# Schematic_v1.net
KiCad netlist of a schematic drawn in Altium Designer
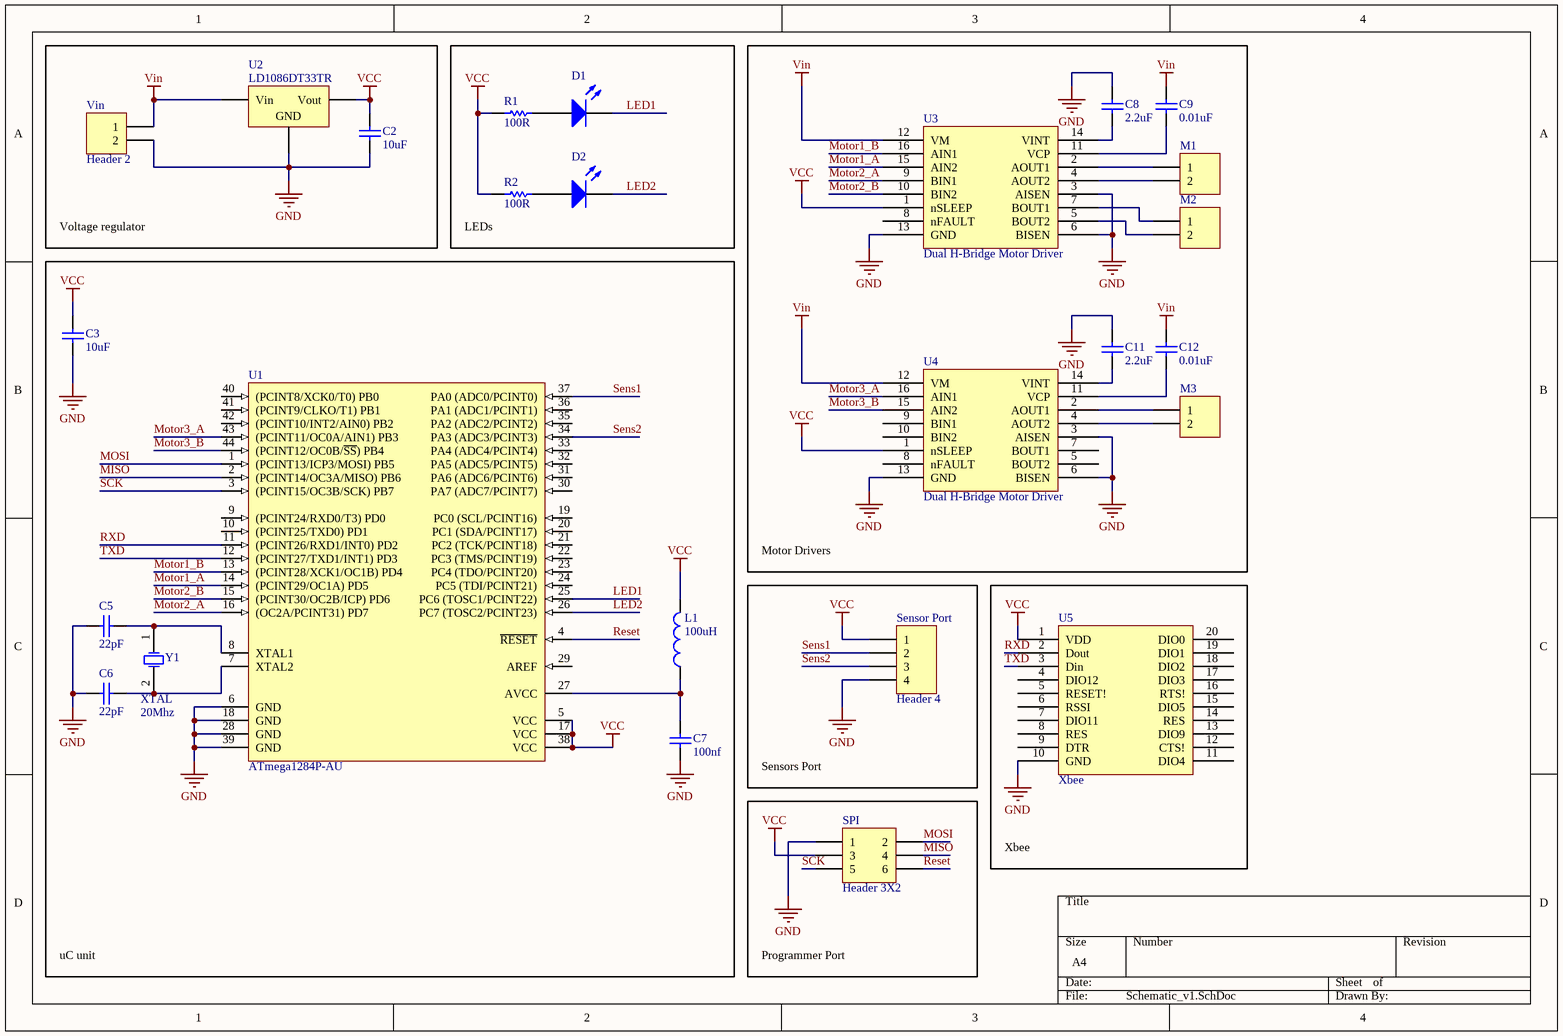
[diagram p0: Schematic_v1.SchDoc]

(export (version "E")
  (design (tool "Eeschema 10.0.6"))
  (components
    (comp (ref "C2")
      (value "10uF")
      (footprint "C1206")
      (description "Capacitor")
      (fields (field (name "Comment") "Cap") (field (name "PUBLISHER") "Altium Limited"))
      (libsource (lib "Miscellaneous Devices") (part "Cap"))
    )
    (comp (ref "C3")
      (value "10uF")
      (footprint "C1206")
      (description "Capacitor")
      (fields (field (name "Comment") "Cap") (field (name "PUBLISHER") "Altium Limited"))
      (libsource (lib "Miscellaneous Devices") (part "Cap"))
    )
    (comp (ref "C5")
      (value "22pF")
      (footprint "C1206")
      (description "Capacitor")
      (fields (field (name "Comment") "Cap") (field (name "PUBLISHER") "Altium Limited"))
      (libsource (lib "Miscellaneous Devices") (part "Cap"))
    )
    (comp (ref "C6")
      (value "22pF")
      (footprint "C1206")
      (description "Capacitor")
      (fields (field (name "Comment") "Cap") (field (name "PUBLISHER") "Altium Limited"))
      (libsource (lib "Miscellaneous Devices") (part "Cap"))
    )
    (comp (ref "C7")
      (value "100nf")
      (footprint "C1206")
      (description "Capacitor")
      (fields (field (name "Comment") "Cap") (field (name "PUBLISHER") "Altium Limited"))
      (libsource (lib "Miscellaneous Devices") (part "Cap"))
    )
    (comp (ref "C8")
      (value "2.2uF")
      (footprint "C1206")
      (description "Capacitor")
      (fields (field (name "Comment") "Cap") (field (name "PUBLISHER") "Altium Limited"))
      (libsource (lib "Miscellaneous Devices") (part "Cap"))
    )
    (comp (ref "C9")
      (value "0.01uF")
      (footprint "C1206")
      (description "Capacitor")
      (fields (field (name "Comment") "Cap") (field (name "PUBLISHER") "Altium Limited"))
      (libsource (lib "Miscellaneous Devices") (part "Cap"))
    )
    (comp (ref "C11")
      (value "2.2uF")
      (footprint "C1206")
      (description "Capacitor")
      (fields (field (name "Comment") "Cap") (field (name "PUBLISHER") "Altium Limited"))
      (libsource (lib "Miscellaneous Devices") (part "Cap"))
    )
    (comp (ref "C12")
      (value "0.01uF")
      (footprint "C1206")
      (description "Capacitor")
      (fields (field (name "Comment") "Cap") (field (name "PUBLISHER") "Altium Limited"))
      (libsource (lib "Miscellaneous Devices") (part "Cap"))
    )
    (comp (ref "D1")
      (value "LED0")
      (footprint "1206")
      (description "Typical INFRARED GaAs LED")
      (fields (field (name "PUBLISHER") "Altium Limited"))
      (libsource (lib "Miscellaneous Devices") (part "LED0"))
    )
    (comp (ref "D2")
      (value "LED0")
      (footprint "1206")
      (description "Typical INFRARED GaAs LED")
      (fields (field (name "PUBLISHER") "Altium Limited"))
      (libsource (lib "Miscellaneous Devices") (part "LED0"))
    )
    (comp (ref "L1")
      (value "100uH")
      (footprint "C0805")
      (description "Inductor")
      (fields (field (name "PUBLISHER") "Altium Limited"))
      (libsource (lib "Miscellaneous Devices") (part "Inductor"))
    )
    (comp (ref "M1")
      (value "Header 2")
      (footprint "SMD Header 2")
      (description "Header, 2-Pin")
      (fields (field (name "PUBLISHER") "Altium Limited"))
      (libsource (lib "Miscellaneous Connectors") (part "Header 2"))
    )
    (comp (ref "M2")
      (value "Header 2")
      (footprint "SMD Header 2")
      (description "Header, 2-Pin")
      (fields (field (name "PUBLISHER") "Altium Limited"))
      (libsource (lib "Miscellaneous Connectors") (part "Header 2"))
    )
    (comp (ref "M3")
      (value "Header 2")
      (footprint "SMD Header 2")
      (description "Header, 2-Pin")
      (fields (field (name "PUBLISHER") "Altium Limited"))
      (libsource (lib "Miscellaneous Connectors") (part "Header 2"))
    )
    (comp (ref "R1")
      (value "100R")
      (footprint "8-1206")
      (description "Resistor")
      (fields (field (name "Comment") "Res1") (field (name "PUBLISHER") "Altium Limited"))
      (libsource (lib "Miscellaneous Devices") (part "Res1"))
    )
    (comp (ref "R2")
      (value "100R")
      (footprint "8-1206")
      (description "Resistor")
      (fields (field (name "Comment") "Res1") (field (name "PUBLISHER") "Altium Limited"))
      (libsource (lib "Miscellaneous Devices") (part "Res1"))
    )
    (comp (ref "Sensor Port")
      (value "Header 4")
      (footprint "SMD HEADER 4")
      (description "Header, 4-Pin")
      (fields (field (name "PUBLISHER") "Altium Limited"))
      (libsource (lib "Miscellaneous Connectors") (part "Header 4"))
    )
    (comp (ref "SPI")
      (value "Header 3X2")
      (footprint "SMD MALE HEADER 3x2")
      (description "Header, 3-Pin, Dual row")
      (fields (field (name "PUBLISHER") "Altium Limited"))
      (libsource (lib "Miscellaneous Connectors") (part "Header 3X2"))
    )
    (comp (ref "U1")
      (value "ATmega1284P-AU")
      (footprint "44A_N")
      (description "20 MHz 8-bit AVR Microcontroller with 128KB Flash, 44-Pin TQFP Pkg, Industrial Temp")
      (fields (field (name "PUBLISHER") "Altium Limited"))
      (libsource (lib "Atmel Communication ICs") (part "ATmega1284P-AU"))
    )
    (comp (ref "U2")
      (value "LD1086DT33TR")
      (footprint "TO-252AA_M")
      (description "Voltage Regulator")
      (fields (field (name "PUBLISHER") "Altium Limited"))
      (libsource (lib "Miscellaneous Devices") (part "Volt Reg"))
    )
    (comp (ref "U3")
      (value "Dual H-Bridge Motor Driver")
      (footprint "TSSOP16_M")
      (libsource (lib "MySchLib") (part "DRV8833"))
    )
    (comp (ref "U4")
      (value "Dual H-Bridge Motor Driver")
      (footprint "TSSOP16_M")
      (libsource (lib "MySchLib") (part "DRV8833"))
    )
    (comp (ref "U5") (value "Xbee") (footprint "Xbee") (libsource (lib "MySchLib") (part "Xbee")))
    (comp (ref "Vin")
      (value "Header 2")
      (footprint "SMD Header 2")
      (description "Header, 2-Pin")
      (fields (field (name "PUBLISHER") "Altium Limited"))
      (libsource (lib "") (part "Header 2_1"))
    )
    (comp (ref "Y1")
      (value "XTAL")
      (footprint "ECX-64A")
      (description "Crystal")
      (fields (field (name "FREQUENCY") "20Mhz") (field (name "PUBLISHER") "Altium Limited"))
      (libsource (lib "Miscellaneous Devices") (part "XTAL"))
    )
  )
  (nets
    (net (code "1") (name "/LED1") (class "Default")
      (node (ref "D1") (pin "2") (pinfunction "K_2") (pintype "passive"))
      (node (ref "U1") (pin "25") (pinfunction "PC6_(TOSC1/PCINT22)_25") (pintype "input"))
    )
    (net (code "2") (name "/LED2") (class "Default")
      (node (ref "D2") (pin "2") (pinfunction "K_2") (pintype "passive"))
      (node (ref "U1") (pin "26") (pinfunction "PC7_(TOSC2/PCINT23)_26") (pintype "input"))
    )
    (net (code "3") (name "/MISO") (class "Default")
      (node (ref "SPI") (pin "4") (pinfunction "4_4") (pintype "passive"))
      (node (ref "U1") (pin "2") (pinfunction "(PCINT14/OC3A/MISO)_PB6_2") (pintype "input"))
    )
    (net (code "4") (name "/MOSI") (class "Default")
      (node (ref "SPI") (pin "2") (pinfunction "2_2") (pintype "passive"))
      (node (ref "U1") (pin "1") (pinfunction "(PCINT13/ICP3/MOSI)_PB5_1") (pintype "input"))
    )
    (net (code "5") (name "/Motor1_A") (class "Default")
      (node (ref "U1") (pin "14") (pinfunction "(PCINT29/OC1A)_PD5_14") (pintype "input"))
      (node (ref "U3") (pin "15") (pinfunction "AIN2_15") (pintype "passive"))
    )
    (net (code "6") (name "/Motor1_B") (class "Default")
      (node (ref "U1") (pin "13") (pinfunction "(PCINT28/XCK1/OC1B)_PD4_13") (pintype "input"))
      (node (ref "U3") (pin "16") (pinfunction "AIN1_16") (pintype "passive"))
    )
    (net (code "7") (name "/Motor2_A") (class "Default")
      (node (ref "U1") (pin "16") (pinfunction "(OC2A/PCINT31)_PD7_16") (pintype "input"))
      (node (ref "U3") (pin "9") (pinfunction "BIN1_9") (pintype "passive"))
    )
    (net (code "8") (name "/Motor2_B") (class "Default")
      (node (ref "U1") (pin "15") (pinfunction "(PCINT30/OC2B/ICP)_PD6_15") (pintype "input"))
      (node (ref "U3") (pin "10") (pinfunction "BIN2_10") (pintype "passive"))
    )
    (net (code "9") (name "/Motor3_A") (class "Default")
      (node (ref "U1") (pin "43") (pinfunction "(PCINT11/OC0A/AIN1)_PB3_43") (pintype "input"))
      (node (ref "U4") (pin "16") (pinfunction "AIN1_16") (pintype "passive"))
    )
    (net (code "10") (name "/Motor3_B") (class "Default")
      (node (ref "U1") (pin "44") (pinfunction "(PCINT12/OC0B/~{SS})_PB4_44") (pintype "input"))
      (node (ref "U4") (pin "15") (pinfunction "AIN2_15") (pintype "passive"))
    )
    (net (code "11") (name "/RXD") (class "Default")
      (node (ref "U1") (pin "11") (pinfunction "(PCINT26/RXD1/INT0)_PD2_11") (pintype "input"))
      (node (ref "U5") (pin "2") (pinfunction "Dout_2") (pintype "passive"))
    )
    (net (code "12") (name "/Reset") (class "Default")
      (node (ref "SPI") (pin "6") (pinfunction "6_6") (pintype "passive"))
      (node (ref "U1") (pin "4") (pinfunction "~{RESET}_4") (pintype "input"))
    )
    (net (code "13") (name "/SCK") (class "Default")
      (node (ref "SPI") (pin "5") (pinfunction "5_5") (pintype "passive"))
      (node (ref "U1") (pin "3") (pinfunction "(PCINT15/OC3B/SCK)_PB7_3") (pintype "input"))
    )
    (net (code "14") (name "/Sens1") (class "Default")
      (node (ref "Sensor Port") (pin "2") (pinfunction "2_2") (pintype "passive"))
      (node (ref "U1") (pin "37") (pinfunction "PA0_(ADC0/PCINT0)_37") (pintype "input"))
    )
    (net (code "15") (name "/Sens2") (class "Default")
      (node (ref "Sensor Port") (pin "3") (pinfunction "3_3") (pintype "passive"))
      (node (ref "U1") (pin "34") (pinfunction "PA3_(ADC3/PCINT3)_34") (pintype "input"))
    )
    (net (code "16") (name "/TXD") (class "Default")
      (node (ref "U1") (pin "12") (pinfunction "(PCINT27/TXD1/INT1)_PD3_12") (pintype "input"))
      (node (ref "U5") (pin "3") (pinfunction "Din_3") (pintype "passive"))
    )
    (net (code "17") (name "GND") (class "Default")
      (node (ref "C11") (pin "2") (pinfunction "2_2") (pintype "passive"))
      (node (ref "C2") (pin "1") (pinfunction "1_1") (pintype "passive"))
      (node (ref "C3") (pin "1") (pinfunction "1_1") (pintype "passive"))
      (node (ref "C5") (pin "1") (pinfunction "1_1") (pintype "passive"))
      (node (ref "C6") (pin "1") (pinfunction "1_1") (pintype "passive"))
      (node (ref "C7") (pin "1") (pinfunction "1_1") (pintype "passive"))
      (node (ref "C8") (pin "2") (pinfunction "2_2") (pintype "passive"))
      (node (ref "SPI") (pin "1") (pinfunction "1_1") (pintype "passive"))
      (node (ref "Sensor Port") (pin "4") (pinfunction "4_4") (pintype "passive"))
      (node (ref "U1") (pin "18") (pinfunction "GND_18") (pintype "passive"))
      (node (ref "U1") (pin "28") (pinfunction "GND_28") (pintype "passive"))
      (node (ref "U1") (pin "39") (pinfunction "GND_39") (pintype "passive"))
      (node (ref "U1") (pin "6") (pinfunction "GND_6") (pintype "passive"))
      (node (ref "U2") (pin "2") (pinfunction "GND_2") (pintype "passive"))
      (node (ref "U3") (pin "13") (pinfunction "GND_13") (pintype "passive"))
      (node (ref "U3") (pin "3") (pinfunction "AISEN_3") (pintype "passive"))
      (node (ref "U3") (pin "6") (pinfunction "BISEN_6") (pintype "passive"))
      (node (ref "U4") (pin "13") (pinfunction "GND_13") (pintype "passive"))
      (node (ref "U4") (pin "3") (pinfunction "AISEN_3") (pintype "passive"))
      (node (ref "U4") (pin "6") (pinfunction "BISEN_6") (pintype "passive"))
      (node (ref "U5") (pin "10") (pinfunction "GND_10") (pintype "passive"))
      (node (ref "Vin") (pin "2") (pinfunction "2_2") (pintype "passive"))
    )
    (net (code "18") (name "Net-(D1-A)") (class "Default")
      (node (ref "D1") (pin "1") (pinfunction "A_1") (pintype "passive"))
      (node (ref "R1") (pin "2") (pinfunction "2_2") (pintype "passive"))
    )
    (net (code "19") (name "Net-(D2-A)") (class "Default")
      (node (ref "D2") (pin "1") (pinfunction "A_1") (pintype "passive"))
      (node (ref "R2") (pin "2") (pinfunction "2_2") (pintype "passive"))
    )
    (net (code "20") (name "Net-(U1-AVCC)") (class "Default")
      (node (ref "C7") (pin "2") (pinfunction "2_2") (pintype "passive"))
      (node (ref "L1") (pin "1") (pinfunction "1_1") (pintype "passive"))
      (node (ref "U1") (pin "27") (pinfunction "AVCC_27") (pintype "passive"))
    )
    (net (code "21") (name "Net-(U1-XTAL1)") (class "Default")
      (node (ref "C5") (pin "2") (pinfunction "2_2") (pintype "passive"))
      (node (ref "U1") (pin "8") (pinfunction "XTAL1_8") (pintype "passive"))
      (node (ref "Y1") (pin "1") (pinfunction "OSC1_1") (pintype "passive"))
    )
    (net (code "22") (name "Net-(U1-XTAL2)") (class "Default")
      (node (ref "C6") (pin "2") (pinfunction "2_2") (pintype "passive"))
      (node (ref "U1") (pin "7") (pinfunction "XTAL2_7") (pintype "passive"))
      (node (ref "Y1") (pin "2") (pinfunction "OSC2_2") (pintype "passive"))
    )
    (net (code "23") (name "Net-(U3-AOUT1)") (class "Default")
      (node (ref "M1") (pin "1") (pinfunction "1_1") (pintype "passive"))
      (node (ref "U3") (pin "2") (pinfunction "AOUT1_2") (pintype "passive"))
    )
    (net (code "24") (name "Net-(U3-AOUT2)") (class "Default")
      (node (ref "M1") (pin "2") (pinfunction "2_2") (pintype "passive"))
      (node (ref "U3") (pin "4") (pinfunction "AOUT2_4") (pintype "passive"))
    )
    (net (code "25") (name "Net-(U3-BOUT1)") (class "Default")
      (node (ref "M2") (pin "1") (pinfunction "1_1") (pintype "passive"))
      (node (ref "U3") (pin "7") (pinfunction "BOUT1_7") (pintype "passive"))
    )
    (net (code "26") (name "Net-(U3-BOUT2)") (class "Default")
      (node (ref "M2") (pin "2") (pinfunction "2_2") (pintype "passive"))
      (node (ref "U3") (pin "5") (pinfunction "BOUT2_5") (pintype "passive"))
    )
    (net (code "27") (name "Net-(U3-VCP)") (class "Default")
      (node (ref "C9") (pin "1") (pinfunction "1_1") (pintype "passive"))
      (node (ref "U3") (pin "11") (pinfunction "VCP_11") (pintype "passive"))
    )
    (net (code "28") (name "Net-(U3-VINT)") (class "Default")
      (node (ref "C8") (pin "1") (pinfunction "1_1") (pintype "passive"))
      (node (ref "U3") (pin "14") (pinfunction "VINT_14") (pintype "passive"))
    )
    (net (code "29") (name "Net-(U4-AOUT1)") (class "Default")
      (node (ref "M3") (pin "1") (pinfunction "1_1") (pintype "passive"))
      (node (ref "U4") (pin "2") (pinfunction "AOUT1_2") (pintype "passive"))
    )
    (net (code "30") (name "Net-(U4-AOUT2)") (class "Default")
      (node (ref "M3") (pin "2") (pinfunction "2_2") (pintype "passive"))
      (node (ref "U4") (pin "4") (pinfunction "AOUT2_4") (pintype "passive"))
    )
    (net (code "31") (name "Net-(U4-VCP)") (class "Default")
      (node (ref "C12") (pin "1") (pinfunction "1_1") (pintype "passive"))
      (node (ref "U4") (pin "11") (pinfunction "VCP_11") (pintype "passive"))
    )
    (net (code "32") (name "Net-(U4-VINT)") (class "Default")
      (node (ref "C11") (pin "1") (pinfunction "1_1") (pintype "passive"))
      (node (ref "U4") (pin "14") (pinfunction "VINT_14") (pintype "passive"))
    )
    (net (code "33") (name "VCC") (class "Default")
      (node (ref "C2") (pin "2") (pinfunction "2_2") (pintype "passive"))
      (node (ref "C3") (pin "2") (pinfunction "2_2") (pintype "passive"))
      (node (ref "L1") (pin "2") (pinfunction "2_2") (pintype "passive"))
      (node (ref "R1") (pin "1") (pinfunction "1_1") (pintype "passive"))
      (node (ref "R2") (pin "1") (pinfunction "1_1") (pintype "passive"))
      (node (ref "SPI") (pin "3") (pinfunction "3_3") (pintype "passive"))
      (node (ref "Sensor Port") (pin "1") (pinfunction "1_1") (pintype "passive"))
      (node (ref "U1") (pin "17") (pinfunction "VCC_17") (pintype "passive"))
      (node (ref "U1") (pin "38") (pinfunction "VCC_38") (pintype "passive"))
      (node (ref "U1") (pin "5") (pinfunction "VCC_5") (pintype "passive"))
      (node (ref "U2") (pin "3") (pinfunction "Vout_3") (pintype "passive"))
      (node (ref "U3") (pin "1") (pinfunction "nSLEEP_1") (pintype "passive"))
      (node (ref "U4") (pin "1") (pinfunction "nSLEEP_1") (pintype "passive"))
      (node (ref "U5") (pin "1") (pinfunction "VDD_1") (pintype "passive"))
    )
    (net (code "34") (name "Vin") (class "Default")
      (node (ref "C12") (pin "2") (pinfunction "2_2") (pintype "passive"))
      (node (ref "C9") (pin "2") (pinfunction "2_2") (pintype "passive"))
      (node (ref "U2") (pin "1") (pinfunction "Vin_1") (pintype "passive"))
      (node (ref "U3") (pin "12") (pinfunction "VM_12") (pintype "passive"))
      (node (ref "U4") (pin "12") (pinfunction "VM_12") (pintype "passive"))
      (node (ref "Vin") (pin "1") (pinfunction "1_1") (pintype "passive"))
    )
    (net (code "35") (name "unconnected-(U1-(PCINT8{slash}XCK0{slash}T0)_PB0-Pad40)") (class "Default")
      (node (ref "U1") (pin "40") (pinfunction "(PCINT8/XCK0/T0)_PB0_40") (pintype "input"))
    )
    (net (code "36") (name "unconnected-(U1-(PCINT9{slash}CLKO{slash}T1)_PB1-Pad41)") (class "Default")
      (node (ref "U1") (pin "41") (pinfunction "(PCINT9/CLKO/T1)_PB1_41") (pintype "input"))
    )
    (net (code "37") (name "unconnected-(U1-(PCINT10{slash}INT2{slash}AIN0)_PB2-Pad42)") (class "Default")
      (node (ref "U1") (pin "42") (pinfunction "(PCINT10/INT2/AIN0)_PB2_42") (pintype "input"))
    )
    (net (code "38") (name "unconnected-(U1-(PCINT24{slash}RXD0{slash}T3)_PD0-Pad9)") (class "Default")
      (node (ref "U1") (pin "9") (pinfunction "(PCINT24/RXD0/T3)_PD0_9") (pintype "input"))
    )
    (net (code "39") (name "unconnected-(U1-(PCINT25{slash}TXD0)_PD1-Pad10)") (class "Default")
      (node (ref "U1") (pin "10") (pinfunction "(PCINT25/TXD0)_PD1_10") (pintype "input"))
    )
    (net (code "40") (name "unconnected-(U1-AREF-Pad29)") (class "Default")
      (node (ref "U1") (pin "29") (pinfunction "AREF_29") (pintype "input"))
    )
    (net (code "41") (name "unconnected-(U1-PA1_(ADC1{slash}PCINT1)-Pad36)") (class "Default")
      (node (ref "U1") (pin "36") (pinfunction "PA1_(ADC1/PCINT1)_36") (pintype "input"))
    )
    (net (code "42") (name "unconnected-(U1-PA2_(ADC2{slash}PCINT2)-Pad35)") (class "Default")
      (node (ref "U1") (pin "35") (pinfunction "PA2_(ADC2/PCINT2)_35") (pintype "input"))
    )
    (net (code "43") (name "unconnected-(U1-PA4_(ADC4{slash}PCINT4)-Pad33)") (class "Default")
      (node (ref "U1") (pin "33") (pinfunction "PA4_(ADC4/PCINT4)_33") (pintype "input"))
    )
    (net (code "44") (name "unconnected-(U1-PA5_(ADC5{slash}PCINT5)-Pad32)") (class "Default")
      (node (ref "U1") (pin "32") (pinfunction "PA5_(ADC5/PCINT5)_32") (pintype "input"))
    )
    (net (code "45") (name "unconnected-(U1-PA6_(ADC6{slash}PCINT6)-Pad31)") (class "Default")
      (node (ref "U1") (pin "31") (pinfunction "PA6_(ADC6/PCINT6)_31") (pintype "input"))
    )
    (net (code "46") (name "unconnected-(U1-PA7_(ADC7{slash}PCINT7)-Pad30)") (class "Default")
      (node (ref "U1") (pin "30") (pinfunction "PA7_(ADC7/PCINT7)_30") (pintype "input"))
    )
    (net (code "47") (name "unconnected-(U1-PC0_(SCL{slash}PCINT16)-Pad19)") (class "Default")
      (node (ref "U1") (pin "19") (pinfunction "PC0_(SCL/PCINT16)_19") (pintype "input"))
    )
    (net (code "48") (name "unconnected-(U1-PC1_(SDA{slash}PCINT17)-Pad20)") (class "Default")
      (node (ref "U1") (pin "20") (pinfunction "PC1_(SDA/PCINT17)_20") (pintype "input"))
    )
    (net (code "49") (name "unconnected-(U1-PC2_(TCK{slash}PCINT18)-Pad21)") (class "Default")
      (node (ref "U1") (pin "21") (pinfunction "PC2_(TCK/PCINT18)_21") (pintype "input"))
    )
    (net (code "50") (name "unconnected-(U1-PC3_(TMS{slash}PCINT19)-Pad22)") (class "Default")
      (node (ref "U1") (pin "22") (pinfunction "PC3_(TMS/PCINT19)_22") (pintype "input"))
    )
    (net (code "51") (name "unconnected-(U1-PC4_(TDO{slash}PCINT20)-Pad23)") (class "Default")
      (node (ref "U1") (pin "23") (pinfunction "PC4_(TDO/PCINT20)_23") (pintype "input"))
    )
    (net (code "52") (name "unconnected-(U1-PC5_(TDI{slash}PCINT21)-Pad24)") (class "Default")
      (node (ref "U1") (pin "24") (pinfunction "PC5_(TDI/PCINT21)_24") (pintype "input"))
    )
    (net (code "53") (name "unconnected-(U3-nFAULT-Pad8)") (class "Default")
      (node (ref "U3") (pin "8") (pinfunction "nFAULT_8") (pintype "passive"))
    )
    (net (code "54") (name "unconnected-(U4-BIN1-Pad9)") (class "Default")
      (node (ref "U4") (pin "9") (pinfunction "BIN1_9") (pintype "passive"))
    )
    (net (code "55") (name "unconnected-(U4-BIN2-Pad10)") (class "Default")
      (node (ref "U4") (pin "10") (pinfunction "BIN2_10") (pintype "passive"))
    )
    (net (code "56") (name "unconnected-(U4-BOUT1-Pad7)") (class "Default")
      (node (ref "U4") (pin "7") (pinfunction "BOUT1_7") (pintype "passive"))
    )
    (net (code "57") (name "unconnected-(U4-BOUT2-Pad5)") (class "Default")
      (node (ref "U4") (pin "5") (pinfunction "BOUT2_5") (pintype "passive"))
    )
    (net (code "58") (name "unconnected-(U4-nFAULT-Pad8)") (class "Default")
      (node (ref "U4") (pin "8") (pinfunction "nFAULT_8") (pintype "passive"))
    )
    (net (code "59") (name "unconnected-(U5-CTS!-Pad12)") (class "Default")
      (node (ref "U5") (pin "12") (pinfunction "CTS!_12") (pintype "passive"))
    )
    (net (code "60") (name "unconnected-(U5-DIO0-Pad20)") (class "Default")
      (node (ref "U5") (pin "20") (pinfunction "DIO0_20") (pintype "passive"))
    )
    (net (code "61") (name "unconnected-(U5-DIO1-Pad19)") (class "Default")
      (node (ref "U5") (pin "19") (pinfunction "DIO1_19") (pintype "passive"))
    )
    (net (code "62") (name "unconnected-(U5-DIO2-Pad18)") (class "Default")
      (node (ref "U5") (pin "18") (pinfunction "DIO2_18") (pintype "passive"))
    )
    (net (code "63") (name "unconnected-(U5-DIO3-Pad17)") (class "Default")
      (node (ref "U5") (pin "17") (pinfunction "DIO3_17") (pintype "passive"))
    )
    (net (code "64") (name "unconnected-(U5-DIO4-Pad11)") (class "Default")
      (node (ref "U5") (pin "11") (pinfunction "DIO4_11") (pintype "passive"))
    )
    (net (code "65") (name "unconnected-(U5-DIO5-Pad15)") (class "Default")
      (node (ref "U5") (pin "15") (pinfunction "DIO5_15") (pintype "passive"))
    )
    (net (code "66") (name "unconnected-(U5-DIO9-Pad13)") (class "Default")
      (node (ref "U5") (pin "13") (pinfunction "DIO9_13") (pintype "passive"))
    )
    (net (code "67") (name "unconnected-(U5-DIO11-Pad7)") (class "Default")
      (node (ref "U5") (pin "7") (pinfunction "DIO11_7") (pintype "passive"))
    )
    (net (code "68") (name "unconnected-(U5-DIO12-Pad4)") (class "Default")
      (node (ref "U5") (pin "4") (pinfunction "DIO12_4") (pintype "passive"))
    )
    (net (code "69") (name "unconnected-(U5-DTR-Pad9)") (class "Default")
      (node (ref "U5") (pin "9") (pinfunction "DTR_9") (pintype "passive"))
    )
    (net (code "70") (name "unconnected-(U5-RES-Pad8)") (class "Default")
      (node (ref "U5") (pin "8") (pinfunction "RES_8") (pintype "passive"))
    )
    (net (code "71") (name "unconnected-(U5-RES-Pad14)") (class "Default")
      (node (ref "U5") (pin "14") (pinfunction "RES_14") (pintype "passive"))
    )
    (net (code "72") (name "unconnected-(U5-RESET!-Pad5)") (class "Default")
      (node (ref "U5") (pin "5") (pinfunction "RESET!_5") (pintype "passive"))
    )
    (net (code "73") (name "unconnected-(U5-RSSI-Pad6)") (class "Default")
      (node (ref "U5") (pin "6") (pinfunction "RSSI_6") (pintype "passive"))
    )
    (net (code "74") (name "unconnected-(U5-RTS!-Pad16)") (class "Default")
      (node (ref "U5") (pin "16") (pinfunction "RTS!_16") (pintype "passive"))
    )
  )
)
